# 32-178_-.net
KiCad netlist of a schematic drawn in Altium Designer
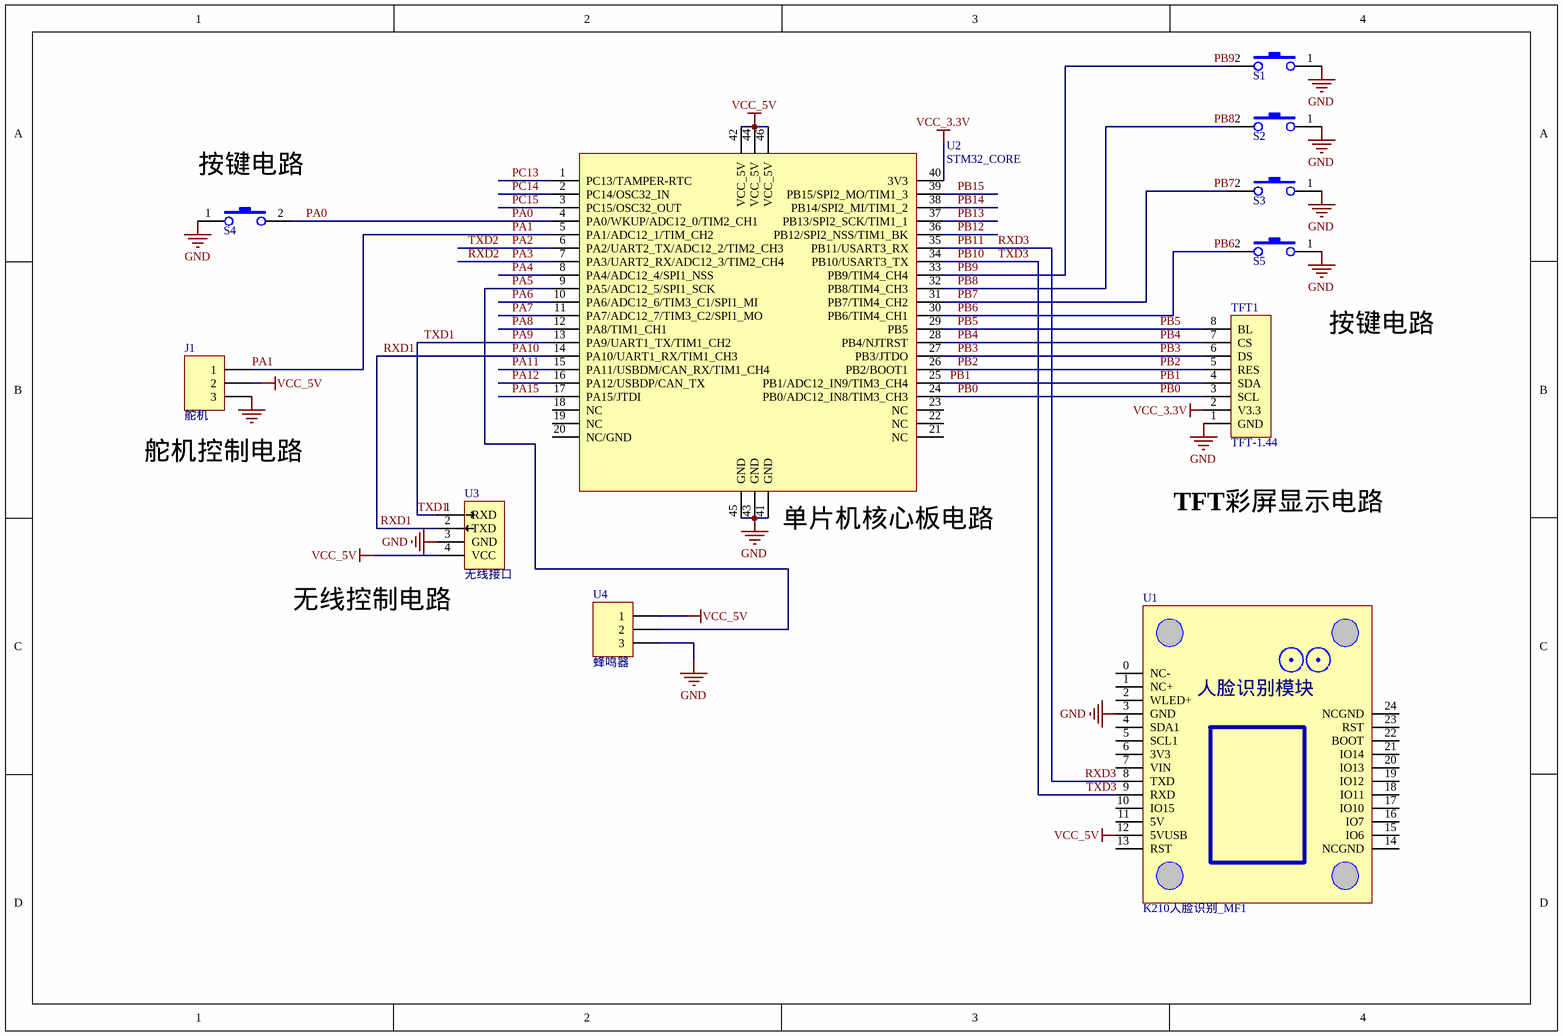
[diagram p0: 32-178原理图（源文件格式） - 副本.SchDoc]

(export (version "E")
  (design (tool "Eeschema 10.0.6"))
  (components
    (comp (ref "J1")
      (value "舵机")
      (footprint "TWKJ_S:舵机接口")
      (description "接线端子3芯")
      (fields (field (name "PUBLISHER") "Altium Limited"))
      (libsource (lib "TWKJ_S") (part "CON3"))
    )
    (comp (ref "S1")
      (value "Button")
      (footprint "TWKJ_S:BUTTON_6x6DIP")
      (description "按键")
      (libsource (lib "TWKJ_S") (part "Button"))
    )
    (comp (ref "S2")
      (value "Button")
      (footprint "TWKJ_S:BUTTON_6x6DIP")
      (description "按键")
      (libsource (lib "TWKJ_S") (part "Button"))
    )
    (comp (ref "S3")
      (value "Button")
      (footprint "TWKJ_S:BUTTON_6x6DIP")
      (description "按键")
      (libsource (lib "TWKJ_S") (part "Button"))
    )
    (comp (ref "S4")
      (value "Button")
      (footprint "TWKJ_S:BUTTON_6x6DIP")
      (description "按键")
      (libsource (lib "TWKJ_S") (part "Button"))
    )
    (comp (ref "S5")
      (value "Button")
      (footprint "TWKJ_S:BUTTON_6x6DIP")
      (description "按键")
      (libsource (lib "TWKJ_S") (part "Button"))
    )
    (comp (ref "TFT1") (value "TFT-1.44") (footprint "TFT-1.44") (libsource (lib "TWKJ_S") (part "TFT-1.44")))
    (comp (ref "U1")
      (value "K210人脸识别_MF1")
      (footprint "K210_MF1")
      (libsource (lib "TWKJ_S") (part "K210人脸识别_MF1"))
    )
    (comp (ref "U2")
      (value "STM32_CORE")
      (footprint "TWKJ_S:STM32_CORE")
      (description "STM32核心板")
      (libsource (lib "TWKJ_S") (part "STM32_CORE"))
    )
    (comp (ref "U3")
      (value "无线接口")
      (footprint "TWKJ_S:蓝牙MODE平放")
      (description "蓝牙模块")
      (libsource (lib "TWKJ_S") (part "蓝牙MODE"))
    )
    (comp (ref "U4")
      (value "蜂鸣器")
      (footprint "TWKJ_S:舵机接口")
      (description "接线端子3芯")
      (fields (field (name "PUBLISHER") "Altium Limited"))
      (libsource (lib "TWKJ_S") (part "CON3"))
    )
  )
  (nets
    (net (code "1") (name "/PA0") (class "Default")
      (node (ref "S4") (pin "2") (pinfunction "2_2") (pintype "passive"))
      (node (ref "U2") (pin "4") (pinfunction "PA0/WKUP/ADC12_0/TIM2_CH1_4") (pintype "passive"))
    )
    (net (code "2") (name "/PA1") (class "Default")
      (node (ref "J1") (pin "1") (pinfunction "1_1") (pintype "passive"))
      (node (ref "U2") (pin "5") (pinfunction "PA1/ADC12_1/TIM_CH2_5") (pintype "passive"))
    )
    (net (code "3") (name "/PA2") (class "Default")
      (node (ref "U2") (pin "6") (pinfunction "PA2/UART2_TX/ADC12_2/TIM2_CH3_6") (pintype "passive"))
    )
    (net (code "4") (name "/PA3") (class "Default")
      (node (ref "U2") (pin "7") (pinfunction "PA3/UART2_RX/ADC12_3/TIM2_CH4_7") (pintype "passive"))
    )
    (net (code "5") (name "/PA4") (class "Default")
      (node (ref "U2") (pin "8") (pinfunction "PA4/ADC12_4/SPI1_NSS_8") (pintype "passive"))
    )
    (net (code "6") (name "/PA5") (class "Default")
      (node (ref "U2") (pin "9") (pinfunction "PA5/ADC12_5/SPI1_SCK_9") (pintype "passive"))
      (node (ref "U4") (pin "2") (pinfunction "2_2") (pintype "passive"))
    )
    (net (code "7") (name "/PA6") (class "Default")
      (node (ref "U2") (pin "10") (pinfunction "PA6/ADC12_6/TIM3_C1/SPI1_MI_10") (pintype "passive"))
    )
    (net (code "8") (name "/PA7") (class "Default")
      (node (ref "U2") (pin "11") (pinfunction "PA7/ADC12_7/TIM3_C2/SPI1_MO_11") (pintype "passive"))
    )
    (net (code "9") (name "/PA8") (class "Default")
      (node (ref "U2") (pin "12") (pinfunction "PA8/TIM1_CH1_12") (pintype "passive"))
    )
    (net (code "10") (name "/PA9") (class "Default")
      (node (ref "U2") (pin "13") (pinfunction "PA9/UART1_TX/TIM1_CH2_13") (pintype "passive"))
      (node (ref "U3") (pin "1") (pinfunction "RXD_1") (pintype "passive"))
    )
    (net (code "11") (name "/PA10") (class "Default")
      (node (ref "U2") (pin "14") (pinfunction "PA10/UART1_RX/TIM1_CH3_14") (pintype "passive"))
      (node (ref "U3") (pin "2") (pinfunction "TXD_2") (pintype "passive"))
    )
    (net (code "12") (name "/PA11") (class "Default")
      (node (ref "U2") (pin "15") (pinfunction "PA11/USBDM/CAN_RX/TIM1_CH4_15") (pintype "passive"))
    )
    (net (code "13") (name "/PA12") (class "Default")
      (node (ref "U2") (pin "16") (pinfunction "PA12/USBDP/CAN_TX_16") (pintype "passive"))
    )
    (net (code "14") (name "/PA15") (class "Default")
      (node (ref "U2") (pin "17") (pinfunction "PA15/JTDI_17") (pintype "passive"))
    )
    (net (code "15") (name "/PB0") (class "Default")
      (node (ref "TFT1") (pin "3") (pinfunction "SCL_3") (pintype "passive"))
      (node (ref "U2") (pin "24") (pinfunction "PB0/ADC12_IN8/TIM3_CH3_24") (pintype "passive"))
    )
    (net (code "16") (name "/PB1") (class "Default")
      (node (ref "TFT1") (pin "4") (pinfunction "SDA_4") (pintype "passive"))
      (node (ref "U2") (pin "25") (pinfunction "PB1/ADC12_IN9/TIM3_CH4_25") (pintype "passive"))
    )
    (net (code "17") (name "/PB2") (class "Default")
      (node (ref "TFT1") (pin "5") (pinfunction "RES_5") (pintype "passive"))
      (node (ref "U2") (pin "26") (pinfunction "PB2/BOOT1_26") (pintype "passive"))
    )
    (net (code "18") (name "/PB3") (class "Default")
      (node (ref "TFT1") (pin "6") (pinfunction "DS_6") (pintype "passive"))
      (node (ref "U2") (pin "27") (pinfunction "PB3/JTDO_27") (pintype "passive"))
    )
    (net (code "19") (name "/PB4") (class "Default")
      (node (ref "TFT1") (pin "7") (pinfunction "CS_7") (pintype "passive"))
      (node (ref "U2") (pin "28") (pinfunction "PB4/NJTRST_28") (pintype "passive"))
    )
    (net (code "20") (name "/PB5") (class "Default")
      (node (ref "TFT1") (pin "8") (pinfunction "BL_8") (pintype "passive"))
      (node (ref "U2") (pin "29") (pinfunction "PB5_29") (pintype "passive"))
    )
    (net (code "21") (name "/PB6") (class "Default")
      (node (ref "S5") (pin "2") (pinfunction "2_2") (pintype "passive"))
      (node (ref "U2") (pin "30") (pinfunction "PB6/TIM4_CH1_30") (pintype "passive"))
    )
    (net (code "22") (name "/PB7") (class "Default")
      (node (ref "S3") (pin "2") (pinfunction "2_2") (pintype "passive"))
      (node (ref "U2") (pin "31") (pinfunction "PB7/TIM4_CH2_31") (pintype "passive"))
    )
    (net (code "23") (name "/PB8") (class "Default")
      (node (ref "S2") (pin "2") (pinfunction "2_2") (pintype "passive"))
      (node (ref "U2") (pin "32") (pinfunction "PB8/TIM4_CH3_32") (pintype "passive"))
    )
    (net (code "24") (name "/PB9") (class "Default")
      (node (ref "S1") (pin "2") (pinfunction "2_2") (pintype "passive"))
      (node (ref "U2") (pin "33") (pinfunction "PB9/TIM4_CH4_33") (pintype "passive"))
    )
    (net (code "25") (name "/PB10") (class "Default")
      (node (ref "U1") (pin "9") (pinfunction "RXD_9") (pintype "passive"))
      (node (ref "U2") (pin "34") (pinfunction "PB10/USART3_TX_34") (pintype "passive"))
    )
    (net (code "26") (name "/PB11") (class "Default")
      (node (ref "U1") (pin "8") (pinfunction "TXD_8") (pintype "passive"))
      (node (ref "U2") (pin "35") (pinfunction "PB11/USART3_RX_35") (pintype "passive"))
    )
    (net (code "27") (name "/PB12") (class "Default")
      (node (ref "U2") (pin "36") (pinfunction "PB12/SPI2_NSS/TIM1_BK_36") (pintype "passive"))
    )
    (net (code "28") (name "/PB13") (class "Default")
      (node (ref "U2") (pin "37") (pinfunction "PB13/SPI2_SCK/TIM1_1_37") (pintype "passive"))
    )
    (net (code "29") (name "/PB14") (class "Default")
      (node (ref "U2") (pin "38") (pinfunction "PB14/SPI2_MI/TIM1_2_38") (pintype "passive"))
    )
    (net (code "30") (name "/PB15") (class "Default")
      (node (ref "U2") (pin "39") (pinfunction "PB15/SPI2_MO/TIM1_3_39") (pintype "passive"))
    )
    (net (code "31") (name "/PC13") (class "Default")
      (node (ref "U2") (pin "1") (pinfunction "PC13/TAMPER-RTC_1") (pintype "passive"))
    )
    (net (code "32") (name "/PC14") (class "Default")
      (node (ref "U2") (pin "2") (pinfunction "PC14/OSC32_IN_2") (pintype "passive"))
    )
    (net (code "33") (name "/PC15") (class "Default")
      (node (ref "U2") (pin "3") (pinfunction "PC15/OSC32_OUT_3") (pintype "passive"))
    )
    (net (code "34") (name "GND") (class "Default")
      (node (ref "J1") (pin "3") (pinfunction "3_3") (pintype "passive"))
      (node (ref "S1") (pin "1") (pinfunction "1_1") (pintype "passive"))
      (node (ref "S2") (pin "1") (pinfunction "1_1") (pintype "passive"))
      (node (ref "S3") (pin "1") (pinfunction "1_1") (pintype "passive"))
      (node (ref "S4") (pin "1") (pinfunction "1_1") (pintype "passive"))
      (node (ref "S5") (pin "1") (pinfunction "1_1") (pintype "passive"))
      (node (ref "TFT1") (pin "1") (pinfunction "GND_1") (pintype "passive"))
      (node (ref "U1") (pin "3") (pinfunction "GND_3") (pintype "passive"))
      (node (ref "U2") (pin "41") (pinfunction "GND_41") (pintype "passive"))
      (node (ref "U2") (pin "43") (pinfunction "GND_43") (pintype "passive"))
      (node (ref "U2") (pin "45") (pinfunction "GND_45") (pintype "passive"))
      (node (ref "U3") (pin "3") (pinfunction "GND_3") (pintype "passive"))
      (node (ref "U4") (pin "3") (pinfunction "3_3") (pintype "passive"))
    )
    (net (code "35") (name "VCC_3.3V") (class "Default")
      (node (ref "TFT1") (pin "2") (pinfunction "V3.3_2") (pintype "passive"))
      (node (ref "U2") (pin "40") (pinfunction "3V3_40") (pintype "passive"))
    )
    (net (code "36") (name "VCC_5V") (class "Default")
      (node (ref "J1") (pin "2") (pinfunction "2_2") (pintype "passive"))
      (node (ref "U1") (pin "12") (pinfunction "5VUSB_12") (pintype "passive"))
      (node (ref "U2") (pin "42") (pinfunction "VCC_5V_42") (pintype "passive"))
      (node (ref "U2") (pin "44") (pinfunction "VCC_5V_44") (pintype "passive"))
      (node (ref "U2") (pin "46") (pinfunction "VCC_5V_46") (pintype "passive"))
      (node (ref "U3") (pin "4") (pinfunction "VCC_4") (pintype "passive"))
      (node (ref "U4") (pin "1") (pinfunction "1_1") (pintype "passive"))
    )
    (net (code "37") (name "unconnected-(U1-3V3-Pad6)") (class "Default")
      (node (ref "U1") (pin "6") (pinfunction "3V3_6") (pintype "passive"))
    )
    (net (code "38") (name "unconnected-(U1-5V-Pad11)") (class "Default")
      (node (ref "U1") (pin "11") (pinfunction "5V_11") (pintype "passive"))
    )
    (net (code "39") (name "unconnected-(U1-BOOT-Pad22)") (class "Default")
      (node (ref "U1") (pin "22") (pinfunction "BOOT_22") (pintype "passive"))
    )
    (net (code "40") (name "unconnected-(U1-IO6-Pad15)") (class "Default")
      (node (ref "U1") (pin "15") (pinfunction "IO6_15") (pintype "passive"))
    )
    (net (code "41") (name "unconnected-(U1-IO7-Pad16)") (class "Default")
      (node (ref "U1") (pin "16") (pinfunction "IO7_16") (pintype "passive"))
    )
    (net (code "42") (name "unconnected-(U1-IO10-Pad17)") (class "Default")
      (node (ref "U1") (pin "17") (pinfunction "IO10_17") (pintype "passive"))
    )
    (net (code "43") (name "unconnected-(U1-IO11-Pad18)") (class "Default")
      (node (ref "U1") (pin "18") (pinfunction "IO11_18") (pintype "passive"))
    )
    (net (code "44") (name "unconnected-(U1-IO12-Pad19)") (class "Default")
      (node (ref "U1") (pin "19") (pinfunction "IO12_19") (pintype "passive"))
    )
    (net (code "45") (name "unconnected-(U1-IO13-Pad20)") (class "Default")
      (node (ref "U1") (pin "20") (pinfunction "IO13_20") (pintype "passive"))
    )
    (net (code "46") (name "unconnected-(U1-IO14-Pad21)") (class "Default")
      (node (ref "U1") (pin "21") (pinfunction "IO14_21") (pintype "passive"))
    )
    (net (code "47") (name "unconnected-(U1-IO15-Pad10)") (class "Default")
      (node (ref "U1") (pin "10") (pinfunction "IO15_10") (pintype "passive"))
    )
    (net (code "48") (name "unconnected-(U1-NC+-Pad1)") (class "Default")
      (node (ref "U1") (pin "1") (pinfunction "NC+_1") (pintype "passive"))
    )
    (net (code "49") (name "unconnected-(U1-NC--Pad0)") (class "Default")
      (node (ref "U1") (pin "0") (pinfunction "NC-_0") (pintype "passive"))
    )
    (net (code "50") (name "unconnected-(U1-NCGND-Pad14)") (class "Default")
      (node (ref "U1") (pin "14") (pinfunction "NCGND_14") (pintype "passive"))
    )
    (net (code "51") (name "unconnected-(U1-NCGND-Pad24)") (class "Default")
      (node (ref "U1") (pin "24") (pinfunction "NCGND_24") (pintype "passive"))
    )
    (net (code "52") (name "unconnected-(U1-RST-Pad13)") (class "Default")
      (node (ref "U1") (pin "13") (pinfunction "RST_13") (pintype "passive"))
    )
    (net (code "53") (name "unconnected-(U1-RST-Pad23)") (class "Default")
      (node (ref "U1") (pin "23") (pinfunction "RST_23") (pintype "passive"))
    )
    (net (code "54") (name "unconnected-(U1-SCL1-Pad5)") (class "Default")
      (node (ref "U1") (pin "5") (pinfunction "SCL1_5") (pintype "passive"))
    )
    (net (code "55") (name "unconnected-(U1-SDA1-Pad4)") (class "Default")
      (node (ref "U1") (pin "4") (pinfunction "SDA1_4") (pintype "passive"))
    )
    (net (code "56") (name "unconnected-(U1-VIN-Pad7)") (class "Default")
      (node (ref "U1") (pin "7") (pinfunction "VIN_7") (pintype "passive"))
    )
    (net (code "57") (name "unconnected-(U1-WLED+-Pad2)") (class "Default")
      (node (ref "U1") (pin "2") (pinfunction "WLED+_2") (pintype "passive"))
    )
    (net (code "58") (name "unconnected-(U2-NC-Pad18)") (class "Default")
      (node (ref "U2") (pin "18") (pinfunction "NC_18") (pintype "passive"))
    )
    (net (code "59") (name "unconnected-(U2-NC-Pad19)") (class "Default")
      (node (ref "U2") (pin "19") (pinfunction "NC_19") (pintype "passive"))
    )
    (net (code "60") (name "unconnected-(U2-NC-Pad21)") (class "Default")
      (node (ref "U2") (pin "21") (pinfunction "NC_21") (pintype "passive"))
    )
    (net (code "61") (name "unconnected-(U2-NC-Pad22)") (class "Default")
      (node (ref "U2") (pin "22") (pinfunction "NC_22") (pintype "passive"))
    )
    (net (code "62") (name "unconnected-(U2-NC-Pad23)") (class "Default")
      (node (ref "U2") (pin "23") (pinfunction "NC_23") (pintype "passive"))
    )
    (net (code "63") (name "unconnected-(U2-NC{slash}GND-Pad20)") (class "Default")
      (node (ref "U2") (pin "20") (pinfunction "NC/GND_20") (pintype "passive"))
    )
  )
)
